# BIGDOGLAYOUT.net
KiCad netlist of a schematic drawn in EAGLE
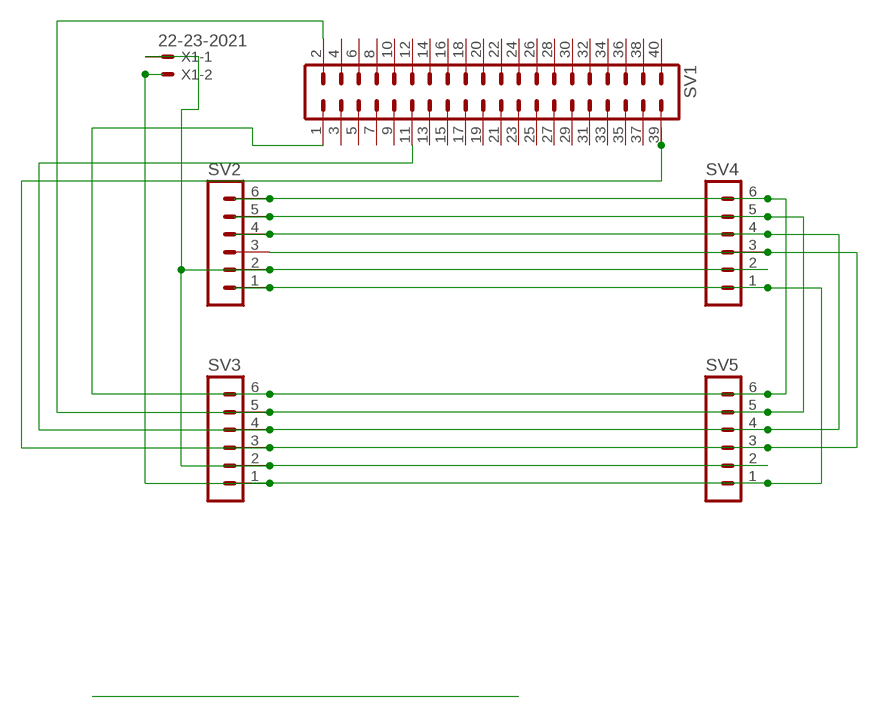
[diagram p0: schematic, sheet 1]

(export (version "E")
  (design (tool "Eeschema 10.0.6"))
  (components
    (comp (ref "SV1")
      (value "MA20-2")
      (footprint "eagle-import:MA20-2")
      (libsource (lib "eagle-import") (part "MA20-2"))
    )
    (comp (ref "SV2")
      (value "MA06-1")
      (footprint "eagle-import:MA06-1")
      (libsource (lib "eagle-import") (part "MA06-1"))
    )
    (comp (ref "SV3")
      (value "MA06-1")
      (footprint "eagle-import:MA06-1")
      (libsource (lib "eagle-import") (part "MA06-1"))
    )
    (comp (ref "SV4")
      (value "MA06-1")
      (footprint "eagle-import:MA06-1")
      (libsource (lib "eagle-import") (part "MA06-1"))
    )
    (comp (ref "SV5")
      (value "MA06-1")
      (footprint "eagle-import:MA06-1")
      (libsource (lib "eagle-import") (part "MA06-1"))
    )
    (comp (ref "X1")
      (value "22-23-2021")
      (footprint "eagle-import:22-23-2021")
      (fields (field (name "MF") "MOLEX"))
      (libsource (lib "eagle-import") (part "22-23-2021"))
    )
  )
  (nets
    (net (code "1") (name "Net-(SV1-Pad1)") (class "Default")
      (node (ref "SV1") (pin "1") (pinfunction "1_1") (pintype "passive"))
      (node (ref "SV2") (pin "6") (pinfunction "6_6") (pintype "passive"))
      (node (ref "SV3") (pin "6") (pinfunction "6_6") (pintype "passive"))
      (node (ref "SV4") (pin "6") (pinfunction "6_6") (pintype "passive"))
      (node (ref "SV5") (pin "6") (pinfunction "6_6") (pintype "passive"))
    )
    (net (code "2") (name "Net-(SV1-Pad2)") (class "Default")
      (node (ref "SV1") (pin "2") (pinfunction "2_2") (pintype "passive"))
      (node (ref "SV2") (pin "5") (pinfunction "5_5") (pintype "passive"))
      (node (ref "SV3") (pin "5") (pinfunction "5_5") (pintype "passive"))
      (node (ref "SV4") (pin "5") (pinfunction "5_5") (pintype "passive"))
      (node (ref "SV5") (pin "5") (pinfunction "5_5") (pintype "passive"))
    )
    (net (code "3") (name "Net-(SV1-Pad11)") (class "Default")
      (node (ref "SV1") (pin "11") (pinfunction "11_11") (pintype "passive"))
      (node (ref "SV2") (pin "4") (pinfunction "4_4") (pintype "passive"))
      (node (ref "SV3") (pin "4") (pinfunction "4_4") (pintype "passive"))
      (node (ref "SV4") (pin "4") (pinfunction "4_4") (pintype "passive"))
      (node (ref "SV5") (pin "4") (pinfunction "4_4") (pintype "passive"))
    )
    (net (code "4") (name "Net-(SV1-Pad39)") (class "Default")
      (node (ref "SV1") (pin "39") (pinfunction "39_39") (pintype "passive"))
      (node (ref "SV2") (pin "3") (pinfunction "3_3") (pintype "passive"))
      (node (ref "SV3") (pin "3") (pinfunction "3_3") (pintype "passive"))
      (node (ref "SV4") (pin "3") (pinfunction "3_3") (pintype "passive"))
      (node (ref "SV5") (pin "3") (pinfunction "3_3") (pintype "passive"))
    )
    (net (code "5") (name "Net-(X1A-S)") (class "Default")
      (node (ref "SV2") (pin "2") (pinfunction "2_2") (pintype "passive"))
      (node (ref "SV3") (pin "2") (pinfunction "2_2") (pintype "passive"))
      (node (ref "SV4") (pin "2") (pinfunction "2_2") (pintype "passive"))
      (node (ref "SV5") (pin "2") (pinfunction "2_2") (pintype "passive"))
      (node (ref "X1") (pin "1") (pinfunction "S_1") (pintype "passive"))
    )
    (net (code "6") (name "Net-(X1B-S)") (class "Default")
      (node (ref "SV2") (pin "1") (pinfunction "1_1") (pintype "passive"))
      (node (ref "SV3") (pin "1") (pinfunction "1_1") (pintype "passive"))
      (node (ref "SV4") (pin "1") (pinfunction "1_1") (pintype "passive"))
      (node (ref "SV5") (pin "1") (pinfunction "1_1") (pintype "passive"))
      (node (ref "X1") (pin "2") (pinfunction "S_2") (pintype "passive"))
    )
    (net (code "7") (name "unconnected-(SV1-Pad3)") (class "Default")
      (node (ref "SV1") (pin "3") (pinfunction "3_3") (pintype "passive"))
    )
    (net (code "8") (name "unconnected-(SV1-Pad4)") (class "Default")
      (node (ref "SV1") (pin "4") (pinfunction "4_4") (pintype "passive"))
    )
    (net (code "9") (name "unconnected-(SV1-Pad5)") (class "Default")
      (node (ref "SV1") (pin "5") (pinfunction "5_5") (pintype "passive"))
    )
    (net (code "10") (name "unconnected-(SV1-Pad6)") (class "Default")
      (node (ref "SV1") (pin "6") (pinfunction "6_6") (pintype "passive"))
    )
    (net (code "11") (name "unconnected-(SV1-Pad7)") (class "Default")
      (node (ref "SV1") (pin "7") (pinfunction "7_7") (pintype "passive"))
    )
    (net (code "12") (name "unconnected-(SV1-Pad8)") (class "Default")
      (node (ref "SV1") (pin "8") (pinfunction "8_8") (pintype "passive"))
    )
    (net (code "13") (name "unconnected-(SV1-Pad9)") (class "Default")
      (node (ref "SV1") (pin "9") (pinfunction "9_9") (pintype "passive"))
    )
    (net (code "14") (name "unconnected-(SV1-Pad10)") (class "Default")
      (node (ref "SV1") (pin "10") (pinfunction "10_10") (pintype "passive"))
    )
    (net (code "15") (name "unconnected-(SV1-Pad12)") (class "Default")
      (node (ref "SV1") (pin "12") (pinfunction "12_12") (pintype "passive"))
    )
    (net (code "16") (name "unconnected-(SV1-Pad13)") (class "Default")
      (node (ref "SV1") (pin "13") (pinfunction "13_13") (pintype "passive"))
    )
    (net (code "17") (name "unconnected-(SV1-Pad14)") (class "Default")
      (node (ref "SV1") (pin "14") (pinfunction "14_14") (pintype "passive"))
    )
    (net (code "18") (name "unconnected-(SV1-Pad15)") (class "Default")
      (node (ref "SV1") (pin "15") (pinfunction "15_15") (pintype "passive"))
    )
    (net (code "19") (name "unconnected-(SV1-Pad16)") (class "Default")
      (node (ref "SV1") (pin "16") (pinfunction "16_16") (pintype "passive"))
    )
    (net (code "20") (name "unconnected-(SV1-Pad17)") (class "Default")
      (node (ref "SV1") (pin "17") (pinfunction "17_17") (pintype "passive"))
    )
    (net (code "21") (name "unconnected-(SV1-Pad18)") (class "Default")
      (node (ref "SV1") (pin "18") (pinfunction "18_18") (pintype "passive"))
    )
    (net (code "22") (name "unconnected-(SV1-Pad19)") (class "Default")
      (node (ref "SV1") (pin "19") (pinfunction "19_19") (pintype "passive"))
    )
    (net (code "23") (name "unconnected-(SV1-Pad20)") (class "Default")
      (node (ref "SV1") (pin "20") (pinfunction "20_20") (pintype "passive"))
    )
    (net (code "24") (name "unconnected-(SV1-Pad21)") (class "Default")
      (node (ref "SV1") (pin "21") (pinfunction "21_21") (pintype "passive"))
    )
    (net (code "25") (name "unconnected-(SV1-Pad22)") (class "Default")
      (node (ref "SV1") (pin "22") (pinfunction "22_22") (pintype "passive"))
    )
    (net (code "26") (name "unconnected-(SV1-Pad23)") (class "Default")
      (node (ref "SV1") (pin "23") (pinfunction "23_23") (pintype "passive"))
    )
    (net (code "27") (name "unconnected-(SV1-Pad24)") (class "Default")
      (node (ref "SV1") (pin "24") (pinfunction "24_24") (pintype "passive"))
    )
    (net (code "28") (name "unconnected-(SV1-Pad25)") (class "Default")
      (node (ref "SV1") (pin "25") (pinfunction "25_25") (pintype "passive"))
    )
    (net (code "29") (name "unconnected-(SV1-Pad26)") (class "Default")
      (node (ref "SV1") (pin "26") (pinfunction "26_26") (pintype "passive"))
    )
    (net (code "30") (name "unconnected-(SV1-Pad27)") (class "Default")
      (node (ref "SV1") (pin "27") (pinfunction "27_27") (pintype "passive"))
    )
    (net (code "31") (name "unconnected-(SV1-Pad28)") (class "Default")
      (node (ref "SV1") (pin "28") (pinfunction "28_28") (pintype "passive"))
    )
    (net (code "32") (name "unconnected-(SV1-Pad29)") (class "Default")
      (node (ref "SV1") (pin "29") (pinfunction "29_29") (pintype "passive"))
    )
    (net (code "33") (name "unconnected-(SV1-Pad30)") (class "Default")
      (node (ref "SV1") (pin "30") (pinfunction "30_30") (pintype "passive"))
    )
    (net (code "34") (name "unconnected-(SV1-Pad31)") (class "Default")
      (node (ref "SV1") (pin "31") (pinfunction "31_31") (pintype "passive"))
    )
    (net (code "35") (name "unconnected-(SV1-Pad32)") (class "Default")
      (node (ref "SV1") (pin "32") (pinfunction "32_32") (pintype "passive"))
    )
    (net (code "36") (name "unconnected-(SV1-Pad33)") (class "Default")
      (node (ref "SV1") (pin "33") (pinfunction "33_33") (pintype "passive"))
    )
    (net (code "37") (name "unconnected-(SV1-Pad34)") (class "Default")
      (node (ref "SV1") (pin "34") (pinfunction "34_34") (pintype "passive"))
    )
    (net (code "38") (name "unconnected-(SV1-Pad35)") (class "Default")
      (node (ref "SV1") (pin "35") (pinfunction "35_35") (pintype "passive"))
    )
    (net (code "39") (name "unconnected-(SV1-Pad36)") (class "Default")
      (node (ref "SV1") (pin "36") (pinfunction "36_36") (pintype "passive"))
    )
    (net (code "40") (name "unconnected-(SV1-Pad37)") (class "Default")
      (node (ref "SV1") (pin "37") (pinfunction "37_37") (pintype "passive"))
    )
    (net (code "41") (name "unconnected-(SV1-Pad38)") (class "Default")
      (node (ref "SV1") (pin "38") (pinfunction "38_38") (pintype "passive"))
    )
    (net (code "42") (name "unconnected-(SV1-Pad40)") (class "Default")
      (node (ref "SV1") (pin "40") (pinfunction "40_40") (pintype "passive"))
    )
  )
)
